# Tiny817_Xplained_Pro_dual_input_power_su.net
KiCad netlist of a schematic drawn in Altium Designer
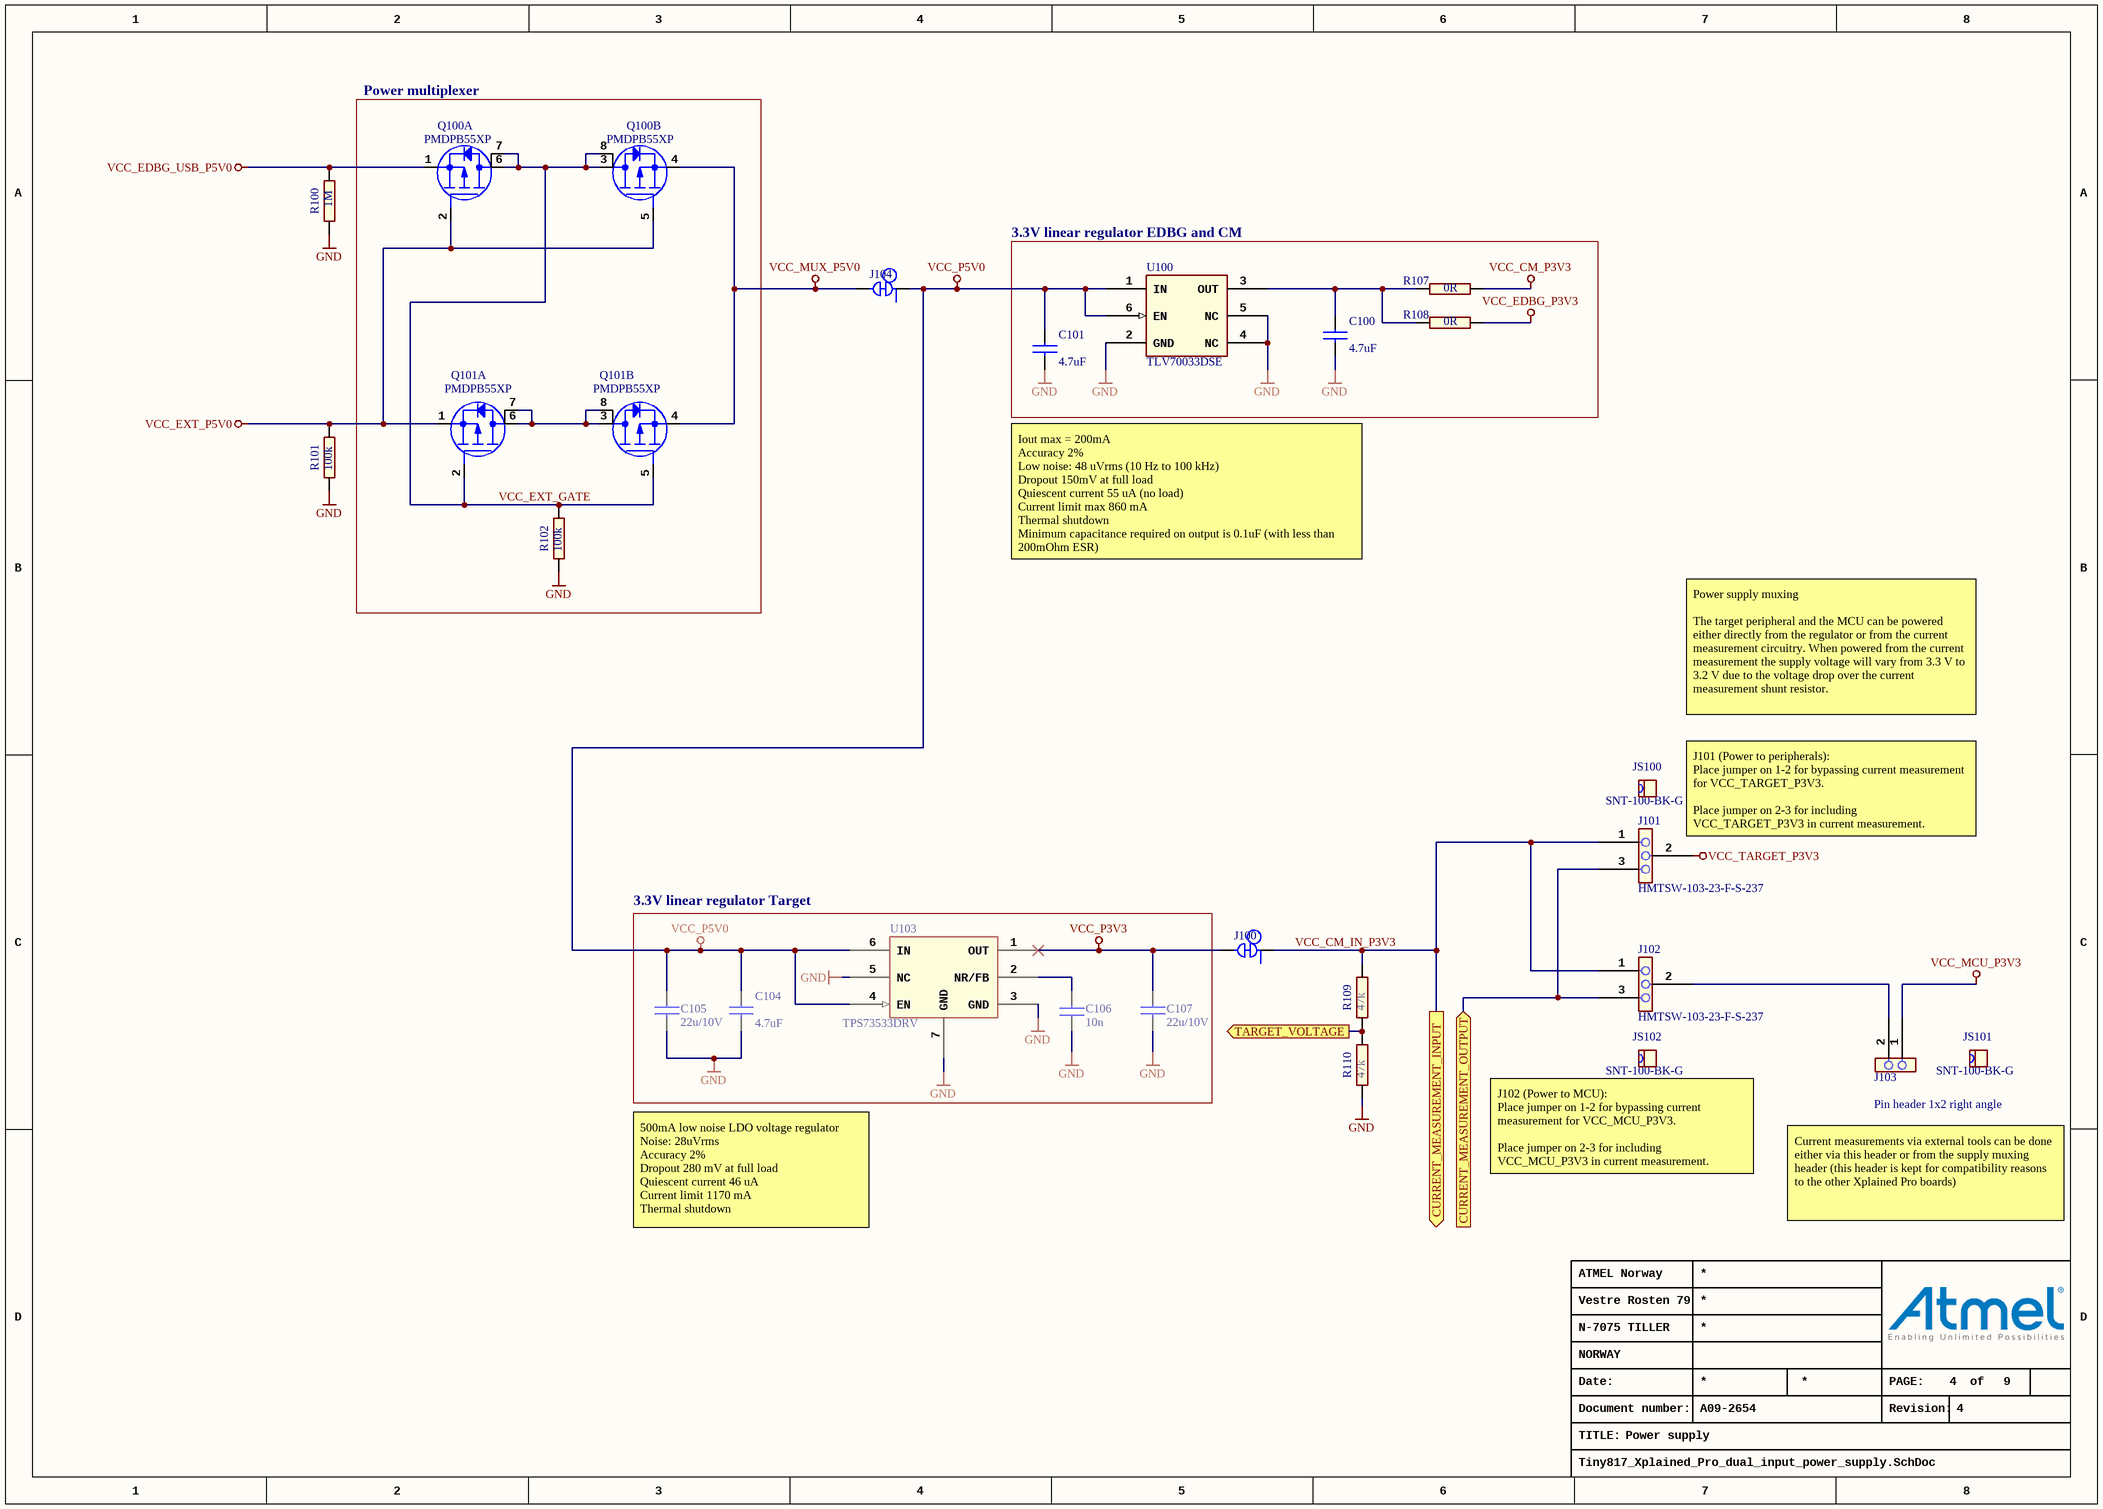
[diagram p0: Tiny817_Xplained_Pro_dual_input_power_supply.SchDoc]

(export (version "E")
  (design (tool "Eeschema 10.0.6"))
  (components
    (comp (ref "C100")
      (value "4.7uF")
      (footprint "AP1-00117")
      (description "Ceramic capacitor, SMD 0603, X5R, 10V, 10% (de31036)")
      (fields (field (name "TOLERANCE") "10%") (field (name "MANUFACTURER") "WALSIN Technology Corporation"))
      (libsource (lib "AltiumDbLib") (part "CAP-NONPOL"))
    )
    (comp (ref "C101")
      (value "4.7uF")
      (footprint "AP1-00117")
      (description "Ceramic capacitor, SMD 0603, X5R, 10V, 10% (de31036)")
      (fields (field (name "TOLERANCE") "10%") (field (name "MANUFACTURER") "WALSIN Technology Corporation"))
      (libsource (lib "AltiumDbLib") (part "CAP-NONPOL"))
    )
    (comp (ref "C104")
      (value "4.7uF")
      (footprint "AP1-00117")
      (description "Ceramic capacitor, SMD 0603, X5R, 10V, 10% (de31036)")
      (fields (field (name "TOLERANCE") "10%") (field (name "MANUFACTURER") "WALSIN Technology Corporation"))
      (libsource (lib "AltiumDbLib") (part "CAP-NONPOL"))
    )
    (comp (ref "C105")
      (value "22u/10V")
      (footprint "AP1-00003")
      (description "Ceramic capacitor, SMD 0805, X5R, 10V, Â±20%")
      (fields (field (name "MANUFACTURER") "tdk") (field (name "MPN") "C2012X5R1A226M/0.85"))
      (libsource (lib "AltiumDbLib") (part "CAP-NONPOL"))
    )
    (comp (ref "C106")
      (value "10n")
      (footprint "AP1-00053")
      (description "Ceramic capacitor, SMD 0402, X7R, 25V, +/-10%")
      (fields (field (name "TOLERANCE") "25V, +/-10%") (field (name "MANUFACTURER") "YAGEO CORP"))
      (libsource (lib "AltiumDbLib") (part "CAP-NONPOL"))
    )
    (comp (ref "C107")
      (value "22u/10V")
      (footprint "AP1-00003")
      (description "Ceramic capacitor, SMD 0805, X5R, 10V, Â±20%")
      (fields (field (name "MANUFACTURER") "tdk") (field (name "MPN") "C2012X5R1A226M/0.85"))
      (libsource (lib "AltiumDbLib") (part "CAP-NONPOL"))
    )
    (comp (ref "J100")
      (value "~")
      (footprint "AP9-00044")
      (description "Default closed SMD strap, 0603 size")
      (libsource (lib "AltiumDbLib") (part "SMD-STRAP_CLOSED"))
    )
    (comp (ref "J101")
      (value "HMTSW-103-23-F-S-237")
      (footprint "AP8-00745")
      (description "1x3 pin header, 2.54mm pitch, Pin-in-Paste THM, 1mm hole")
      (fields (field (name "MANUFACTURER") "SAMTEC"))
      (libsource (lib "AltiumDbLib") (part "HEADER 1x3"))
    )
    (comp (ref "J102")
      (value "HMTSW-103-23-F-S-237")
      (footprint "AP8-00745")
      (description "1x3 pin header, 2.54mm pitch, Pin-in-Paste THM, 1mm hole")
      (fields (field (name "MANUFACTURER") "SAMTEC"))
      (libsource (lib "AltiumDbLib") (part "HEADER 1x3"))
    )
    (comp (ref "J103")
      (value "Pin header 1x2 right angle")
      (footprint "AP8-00367")
      (description "1x2 pin header, right angle, 2.54 mm pitch, through-hole")
      (fields (field (name "MANUFACTURER") "Pro-data International Corp") (field (name "MPN") "2213R-2G"))
      (libsource (lib "AltiumDbLib") (part "HEADER 1x2"))
    )
    (comp (ref "J104")
      (value "~")
      (footprint "AP9-00044")
      (description "Default closed SMD strap, 0603 size")
      (libsource (lib "AltiumDbLib") (part "SMD-STRAP_CLOSED"))
    )
    (comp (ref "JS100")
      (value "SNT-100-BK-G")
      (footprint "AP8-00525")
      (description "Jumper cap for 2.54mm pinheader")
      (fields (field (name "MANUFACTURER") "SAMTEC"))
      (libsource (lib "AltiumDbLib") (part "JUMPER_CAP"))
    )
    (comp (ref "JS101")
      (value "SNT-100-BK-G")
      (footprint "AP8-00525")
      (description "Jumper cap for 2.54mm pinheader")
      (fields (field (name "MANUFACTURER") "SAMTEC"))
      (libsource (lib "AltiumDbLib") (part "JUMPER_CAP"))
    )
    (comp (ref "JS102")
      (value "SNT-100-BK-G")
      (footprint "AP8-00525")
      (description "Jumper cap for 2.54mm pinheader")
      (fields (field (name "MANUFACTURER") "SAMTEC"))
      (libsource (lib "AltiumDbLib") (part "JUMPER_CAP"))
    )
    (comp (ref "Q100")
      (value "PMDPB55XP")
      (footprint "AP5-00047")
      (description "Dual P-Channel MOSFET, -20V, RDS(ON) < 55 mOhm @-3.4A@-4.5V")
      (fields (field (name "MANUFACTURER") "NXP") (field (name "Comment") "Farnell order code: 2191806"))
      (libsource (lib "AltiumDbLib") (part "MOSFET_DUAL_P_S1G1D2S2G2D1D1D2"))
    )
    (comp (ref "Q101")
      (value "PMDPB55XP")
      (footprint "AP5-00047")
      (description "Dual P-Channel MOSFET, -20V, RDS(ON) < 55 mOhm @-3.4A@-4.5V")
      (fields (field (name "MANUFACTURER") "NXP") (field (name "Comment") "Farnell order code: 2191806"))
      (libsource (lib "AltiumDbLib") (part "MOSFET_DUAL_P_S1G1D2S2G2D1D1D2"))
    )
    (comp (ref "R100")
      (value "1M")
      (footprint "AP2-00011")
      (description "Thick film resistor, SMD 0402, 1/16W, 1%")
      (fields (field (name "TOLERANCE") "1 %") (field (name "MANUFACTURER") "ASJ"))
      (libsource (lib "") (part "R2_2"))
    )
    (comp (ref "R101")
      (value "100k")
      (footprint "AP2-00011")
      (description "Thick film resistor, SMD 0402, 1/16W, 1%")
      (fields (field (name "TOLERANCE") "1 %") (field (name "MANUFACTURER") "ASJ"))
      (libsource (lib "") (part "R2_2"))
    )
    (comp (ref "R102")
      (value "100k")
      (footprint "AP2-00011")
      (description "Thick film resistor, SMD 0402, 1/16W, 1%")
      (fields (field (name "TOLERANCE") "1 %") (field (name "MANUFACTURER") "ASJ"))
      (libsource (lib "") (part "R2_2"))
    )
    (comp (ref "R107")
      (value "0R")
      (footprint "AP2-00011")
      (description "RES 0.0 OHM 1/16W 0402 SMD")
      (fields (field (name "TOLERANCE") "1 %") (field (name "MANUFACTURER") "(n/a)"))
      (libsource (lib "AltiumDbLib") (part "R2"))
    )
    (comp (ref "R108")
      (value "0R")
      (footprint "AP2-00011")
      (description "RES 0.0 OHM 1/16W 0402 SMD")
      (fields (field (name "TOLERANCE") "1 %") (field (name "MANUFACTURER") "(n/a)"))
      (libsource (lib "AltiumDbLib") (part "R2"))
    )
    (comp (ref "R109")
      (value "47k")
      (footprint "AP2-00011")
      (description "Thick film resistor, SMD 0402, 1/16W, 1%")
      (fields (field (name "TOLERANCE") "1 %") (field (name "MANUFACTURER") "KOA"))
      (libsource (lib "") (part "R2_1"))
    )
    (comp (ref "R110")
      (value "47k")
      (footprint "AP2-00011")
      (description "Thick film resistor, SMD 0402, 1/16W, 1%")
      (fields (field (name "TOLERANCE") "1 %") (field (name "MANUFACTURER") "KOA"))
      (libsource (lib "") (part "R2_1"))
    )
    (comp (ref "U100")
      (value "TLV70033DSE")
      (footprint "AP6-00262")
      (description "LDO, 200 mA, Iq=31 uA, Vdo=250mV, Vout=3.3V, VIN= 2 V to 5.5V, SON-6 package")
      (fields (field (name "MANUFACTURER") "Texas Instruments"))
      (libsource (lib "AltiumDbLib") (part "TLV70033"))
    )
    (comp (ref "U103")
      (value "TPS73533DRV")
      (footprint "AP6-00162")
      (fields (field (name "MANUFACTURER") "Texas Instruments"))
      (libsource (lib "AltiumDbLib") (part "TPS735xxDRV"))
    )
  )
  (nets
    (net (code "1") (name "/CURRENT_MEASUREMENT_OUTPUT") (class "Default")
      (node (ref "J101") (pin "3") (pinfunction "3_3") (pintype "passive"))
      (node (ref "J102") (pin "3") (pinfunction "3_3") (pintype "passive"))
    )
    (net (code "2") (name "/TARGET_VOLTAGE") (class "Default")
      (node (ref "R109") (pin "1") (pinfunction "1_1") (pintype "passive"))
      (node (ref "R110") (pin "2") (pinfunction "2_2") (pintype "passive"))
    )
    (net (code "3") (name "/VCC_CM_IN_P3V3") (class "Default")
      (node (ref "J100") (pin "1") (pinfunction "1_1") (pintype "passive"))
      (node (ref "J101") (pin "1") (pinfunction "1_1") (pintype "passive"))
      (node (ref "J102") (pin "1") (pinfunction "1_1") (pintype "passive"))
      (node (ref "R109") (pin "2") (pinfunction "2_2") (pintype "passive"))
    )
    (net (code "4") (name "/VCC_EXT_GATE") (class "Default")
      (node (ref "Q100") (pin "3") (pinfunction "D2_3") (pintype "passive"))
      (node (ref "Q100") (pin "6") (pinfunction "D1_6") (pintype "passive"))
      (node (ref "Q100") (pin "7") (pinfunction "D1_PAD_7") (pintype "passive"))
      (node (ref "Q100") (pin "8") (pinfunction "D2_PAD_8") (pintype "passive"))
      (node (ref "Q101") (pin "2") (pinfunction "G1_2") (pintype "passive"))
      (node (ref "Q101") (pin "5") (pinfunction "G2_5") (pintype "passive"))
      (node (ref "R102") (pin "2") (pinfunction "2_2") (pintype "passive"))
    )
    (net (code "5") (name "GND") (class "Default")
      (node (ref "C100") (pin "2") (pinfunction "2_2") (pintype "passive"))
      (node (ref "C101") (pin "2") (pinfunction "2_2") (pintype "passive"))
      (node (ref "C104") (pin "2") (pinfunction "2_2") (pintype "passive"))
      (node (ref "C105") (pin "2") (pinfunction "2_2") (pintype "passive"))
      (node (ref "C106") (pin "1") (pinfunction "1_1") (pintype "passive"))
      (node (ref "C107") (pin "2") (pinfunction "2_2") (pintype "passive"))
      (node (ref "R100") (pin "1") (pinfunction "1_1") (pintype "passive"))
      (node (ref "R101") (pin "1") (pinfunction "1_1") (pintype "passive"))
      (node (ref "R102") (pin "1") (pinfunction "1_1") (pintype "passive"))
      (node (ref "R110") (pin "1") (pinfunction "1_1") (pintype "passive"))
      (node (ref "U100") (pin "2") (pinfunction "GND_2") (pintype "power_in"))
      (node (ref "U100") (pin "4") (pinfunction "NC_4") (pintype "passive"))
      (node (ref "U100") (pin "5") (pinfunction "NC_5") (pintype "passive"))
      (node (ref "U103") (pin "3") (pinfunction "GND_3") (pintype "power_in"))
      (node (ref "U103") (pin "5") (pinfunction "NC_5") (pintype "passive"))
      (node (ref "U103") (pin "7") (pinfunction "GND_7") (pintype "power_in"))
    )
    (net (code "6") (name "Net-(J102-Pad2)") (class "Default")
      (node (ref "J102") (pin "2") (pinfunction "2_2") (pintype "passive"))
      (node (ref "J103") (pin "2") (pinfunction "2_2") (pintype "passive"))
    )
    (net (code "7") (name "Net-(Q101A-D1)") (class "Default")
      (node (ref "Q101") (pin "3") (pinfunction "D2_3") (pintype "passive"))
      (node (ref "Q101") (pin "6") (pinfunction "D1_6") (pintype "passive"))
      (node (ref "Q101") (pin "7") (pinfunction "D1_PAD_7") (pintype "passive"))
      (node (ref "Q101") (pin "8") (pinfunction "D2_PAD_8") (pintype "passive"))
    )
    (net (code "8") (name "Net-(U100-OUT)") (class "Default")
      (node (ref "C100") (pin "1") (pinfunction "1_1") (pintype "passive"))
      (node (ref "R107") (pin "2") (pinfunction "2_2") (pintype "passive"))
      (node (ref "R108") (pin "2") (pinfunction "2_2") (pintype "passive"))
      (node (ref "U100") (pin "3") (pinfunction "OUT_3") (pintype "power_in"))
    )
    (net (code "9") (name "Net-(U103-NR{slash}FB)") (class "Default")
      (node (ref "C106") (pin "2") (pinfunction "2_2") (pintype "passive"))
      (node (ref "U103") (pin "2") (pinfunction "NR/FB_2") (pintype "passive"))
    )
    (net (code "10") (name "VCC_CM_P3V3") (class "Default")
      (node (ref "R107") (pin "1") (pinfunction "1_1") (pintype "passive"))
    )
    (net (code "11") (name "VCC_EDBG_P3V3") (class "Default")
      (node (ref "R108") (pin "1") (pinfunction "1_1") (pintype "passive"))
    )
    (net (code "12") (name "VCC_EDBG_USB_P5V0") (class "Default")
      (node (ref "Q100") (pin "1") (pinfunction "S1_1") (pintype "passive"))
      (node (ref "R100") (pin "2") (pinfunction "2_2") (pintype "passive"))
    )
    (net (code "13") (name "VCC_EXT_P5V0") (class "Default")
      (node (ref "Q100") (pin "2") (pinfunction "G1_2") (pintype "passive"))
      (node (ref "Q100") (pin "5") (pinfunction "G2_5") (pintype "passive"))
      (node (ref "Q101") (pin "1") (pinfunction "S1_1") (pintype "passive"))
      (node (ref "R101") (pin "2") (pinfunction "2_2") (pintype "passive"))
    )
    (net (code "14") (name "VCC_MCU_P3V3") (class "Default")
      (node (ref "J103") (pin "1") (pinfunction "1_1") (pintype "passive"))
    )
    (net (code "15") (name "VCC_MUX_P5V0") (class "Default")
      (node (ref "J104") (pin "2") (pinfunction "2_2") (pintype "passive"))
      (node (ref "Q100") (pin "4") (pinfunction "S2_4") (pintype "passive"))
      (node (ref "Q101") (pin "4") (pinfunction "S2_4") (pintype "passive"))
    )
    (net (code "16") (name "VCC_P3V3") (class "Default")
      (node (ref "C107") (pin "1") (pinfunction "1_1") (pintype "passive"))
      (node (ref "J100") (pin "2") (pinfunction "2_2") (pintype "passive"))
      (node (ref "U103") (pin "1") (pinfunction "OUT_1") (pintype "power_in"))
    )
    (net (code "17") (name "VCC_P5V0") (class "Default")
      (node (ref "C101") (pin "1") (pinfunction "1_1") (pintype "passive"))
      (node (ref "C104") (pin "1") (pinfunction "1_1") (pintype "passive"))
      (node (ref "C105") (pin "1") (pinfunction "1_1") (pintype "passive"))
      (node (ref "J104") (pin "1") (pinfunction "1_1") (pintype "passive"))
      (node (ref "U100") (pin "1") (pinfunction "IN_1") (pintype "power_in"))
      (node (ref "U100") (pin "6") (pinfunction "EN_6") (pintype "input"))
      (node (ref "U103") (pin "4") (pinfunction "EN_4") (pintype "input"))
      (node (ref "U103") (pin "6") (pinfunction "IN_6") (pintype "power_in"))
    )
    (net (code "18") (name "VCC_TARGET_P3V3") (class "Default")
      (node (ref "J101") (pin "2") (pinfunction "2_2") (pintype "passive"))
    )
  )
)
